# schematic.net
KiCad netlist of a schematic drawn in EAGLE
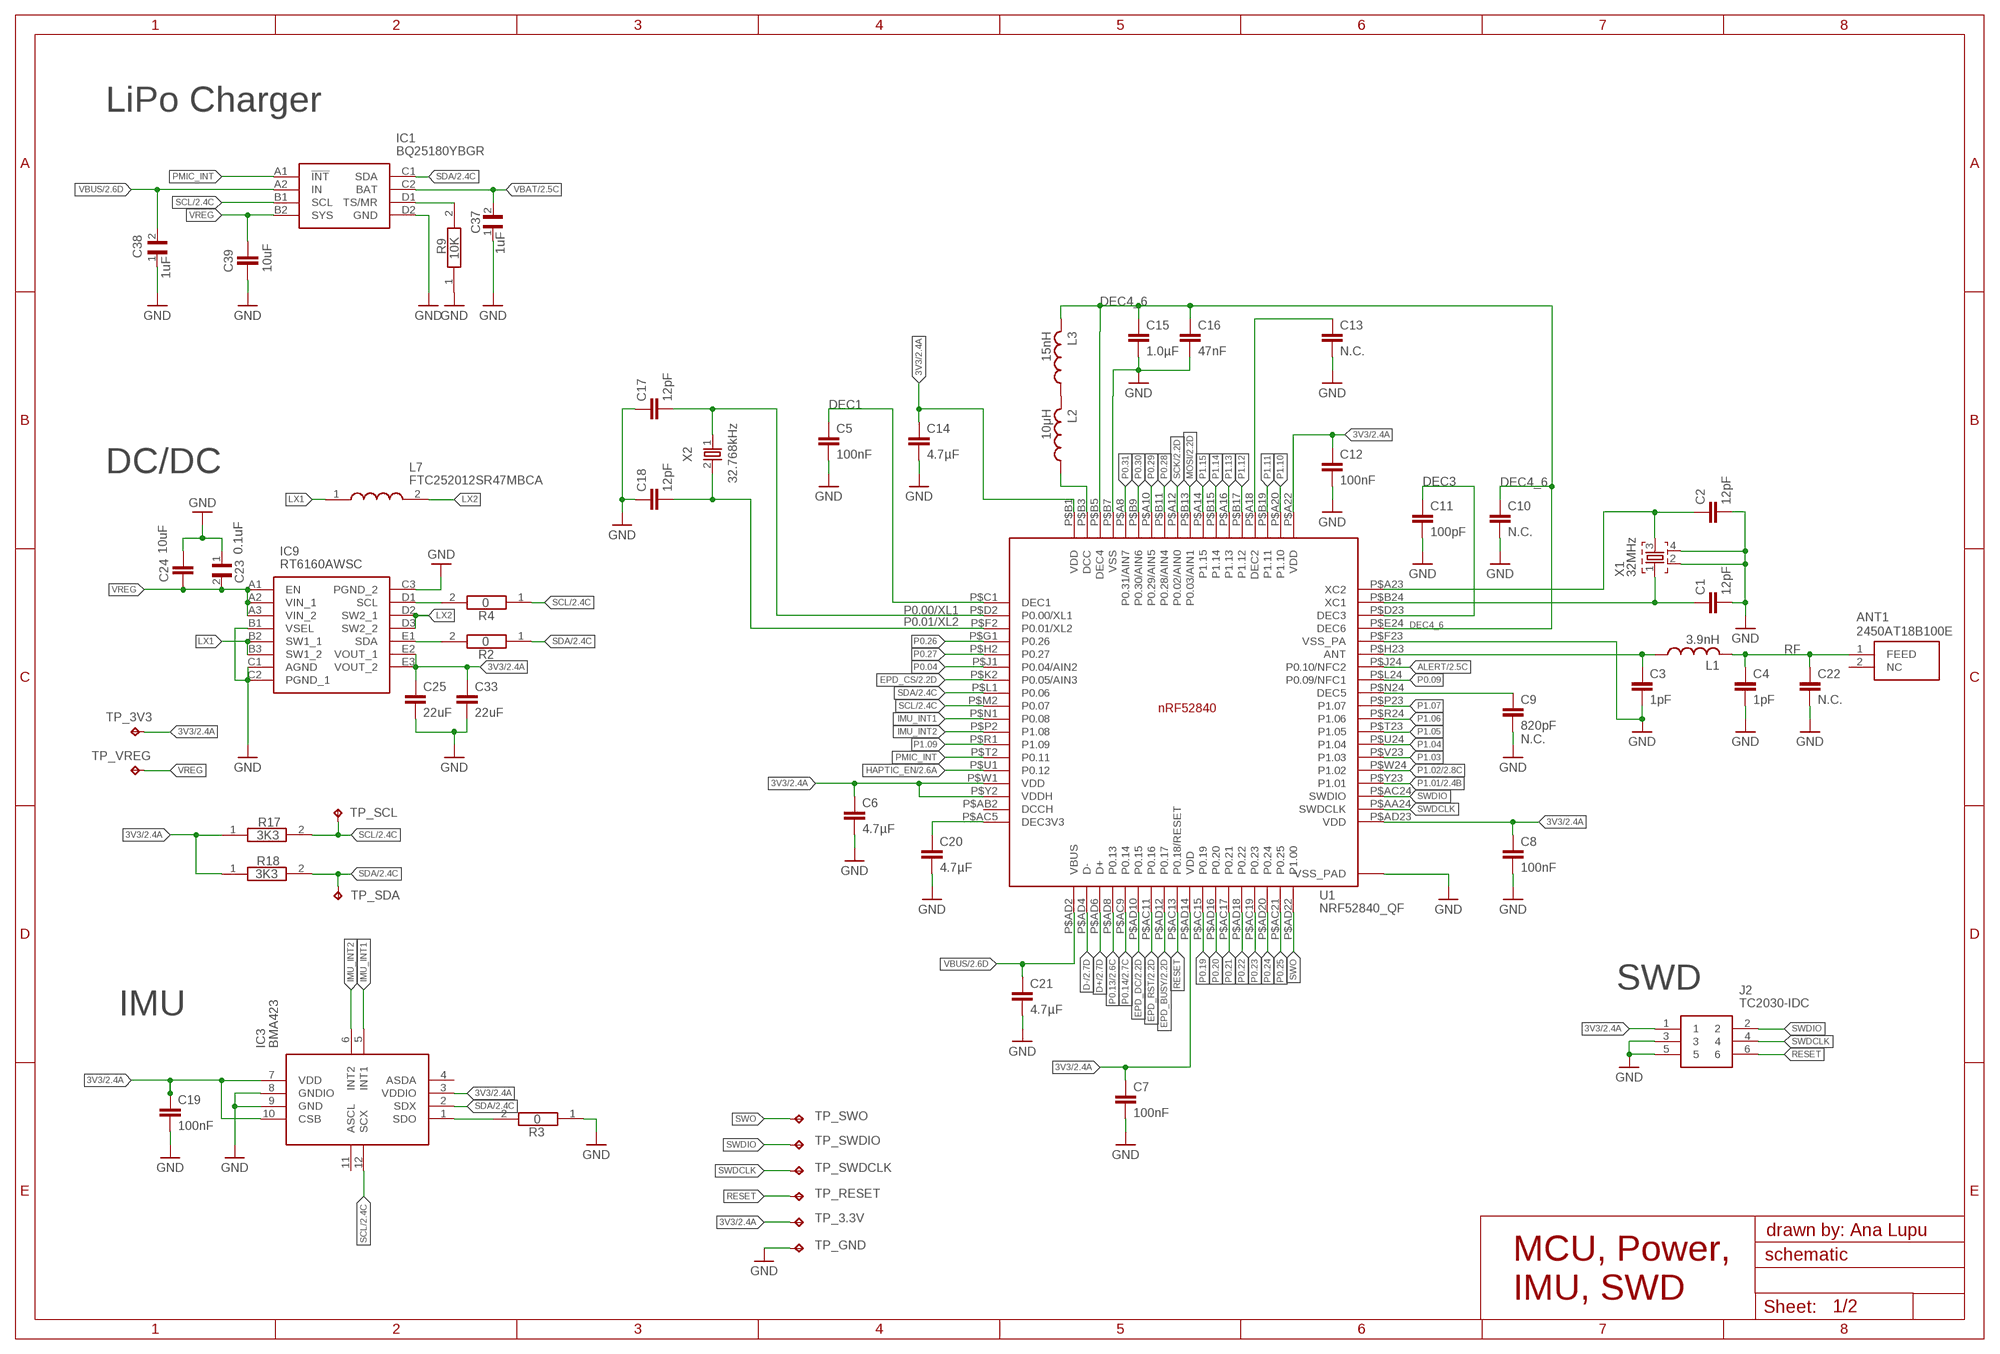
[diagram p0: schematic, sheet 1]
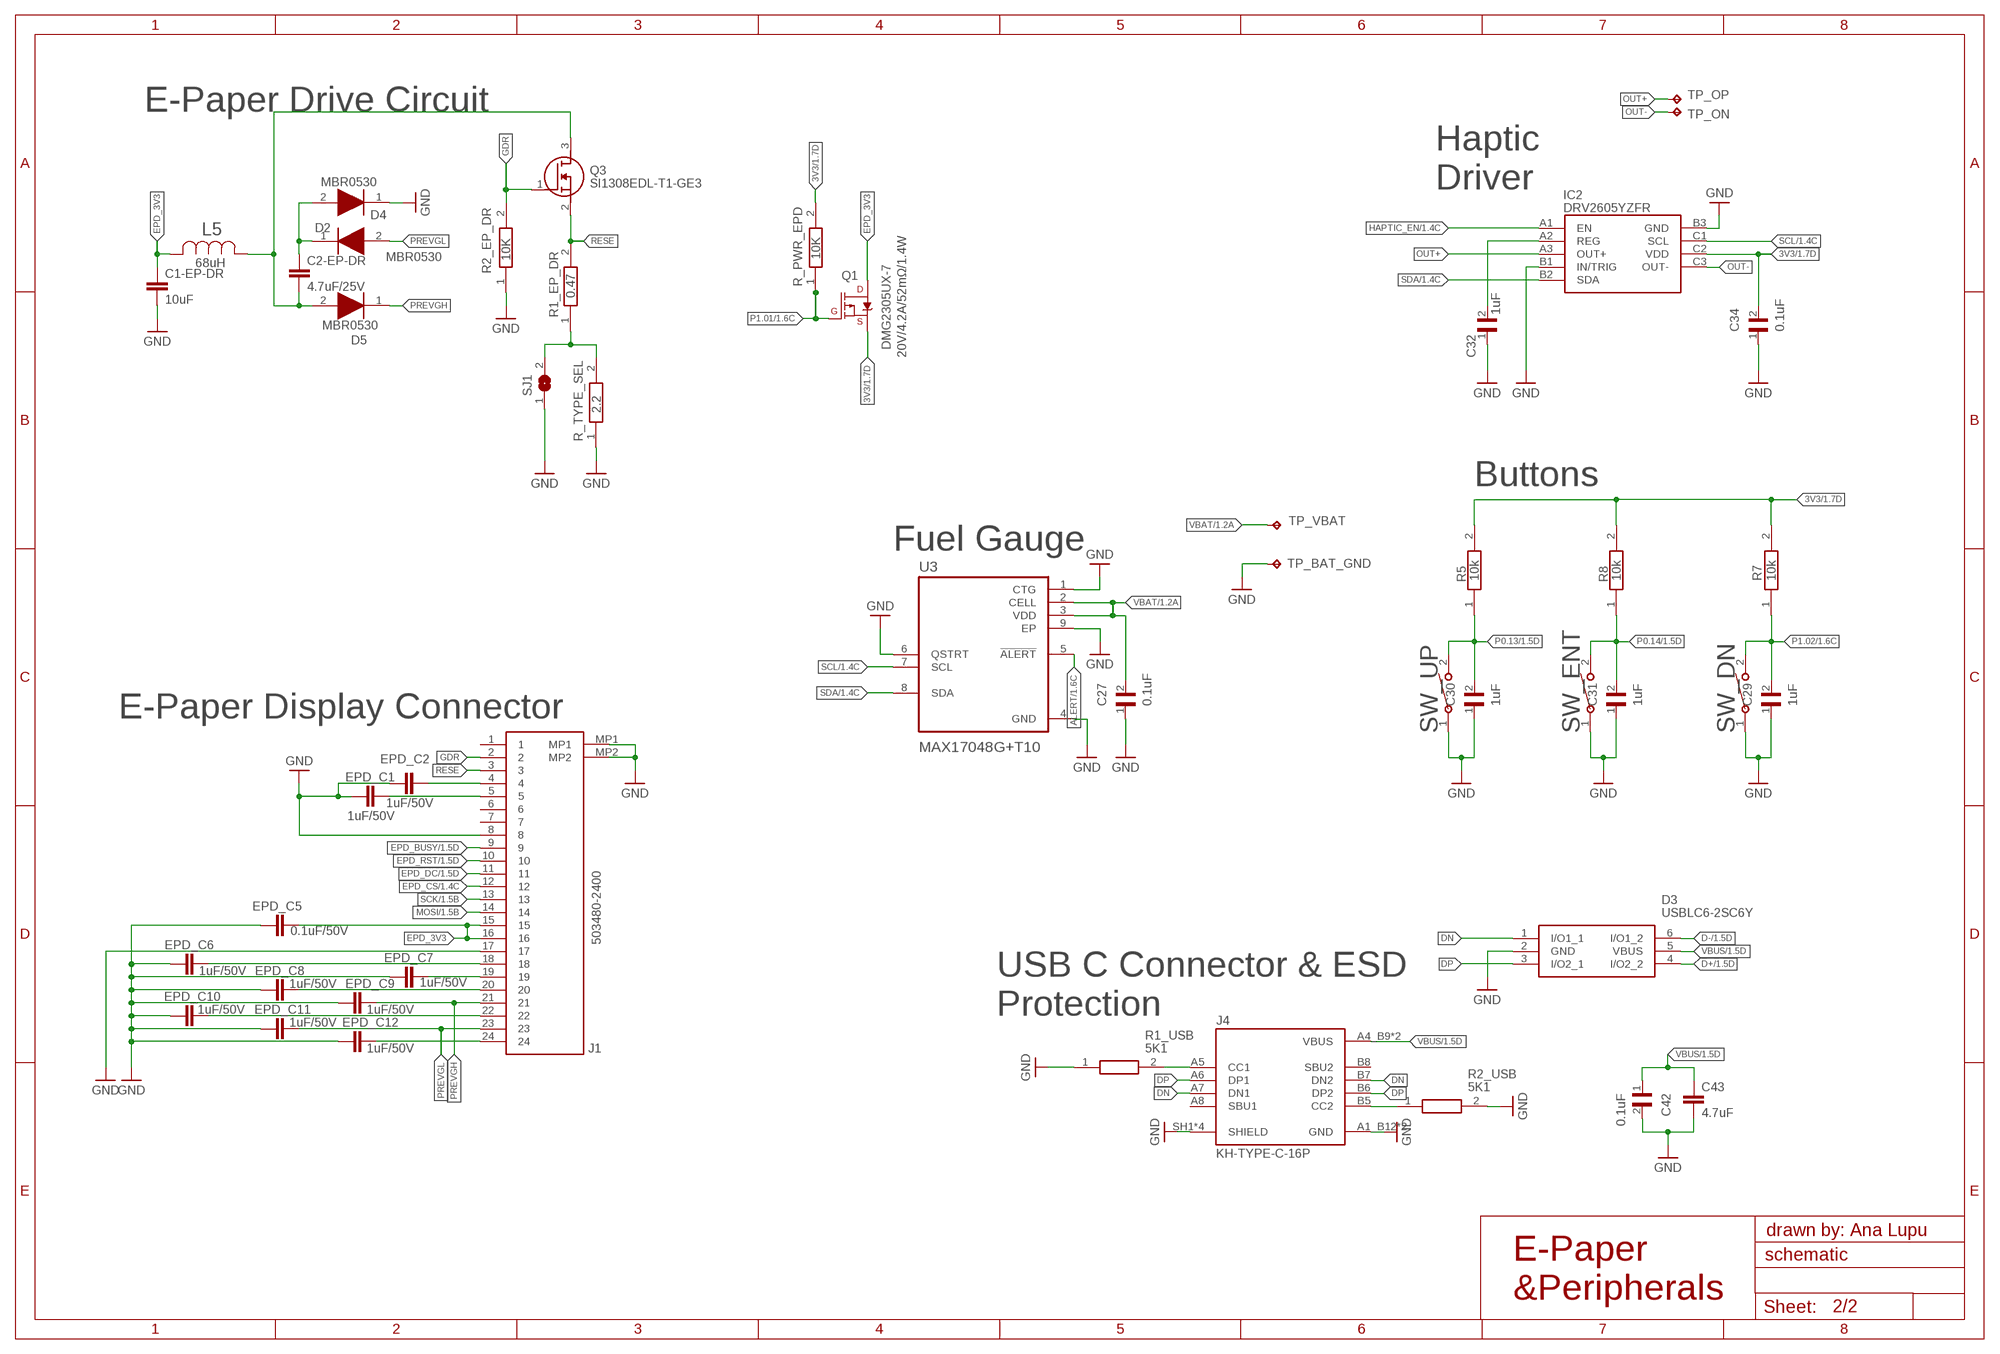
[diagram p1: schematic, sheet 2]

(export (version "E")
  (design (tool "Eeschema 10.0.6"))
  (components
    (comp (ref "C1-EP-DR")
      (value "10uF")
      (footprint "eagle-import:PERFECT_0402_0402")
      (libsource (lib "eagle-import") (part "InkTime_v5_vf.vX5wmjY0RqGaybr4i_JXZQ_PERFECT_0402_CAP_0402"))
    )
    (comp (ref "C2-EP-DR")
      (value "4.7uF/25V")
      (footprint "eagle-import:PERFECT_0402_0402")
      (libsource (lib "eagle-import") (part "InkTime_v5_vf.vX5wmjY0RqGaybr4i_JXZQ_PERFECT_0402_CAP_0402"))
    )
    (comp (ref "C27")
      (value "0.1uF")
      (footprint "eagle-import:GRM011R60J152KE01L_2_CAPC0201X13N")
      (fields (field (name "MF") "Murata") (field (name "MP") "GRM011R60J152KE01L"))
      (libsource (lib "eagle-import") (part "GRM011R60J152KE01L_2_GRM011R60J152KE01L"))
    )
    (comp (ref "C29")
      (value "1uF")
      (footprint "eagle-import:GRM011R60J152KE01L_2_CAPC0201X13N")
      (fields (field (name "MF") "Murata") (field (name "MP") "GRM011R60J152KE01L"))
      (libsource (lib "eagle-import") (part "GRM011R60J152KE01L_2_GRM011R60J152KE01L"))
    )
    (comp (ref "C30")
      (value "1uF")
      (footprint "eagle-import:GRM011R60J152KE01L_2_CAPC0201X13N")
      (fields (field (name "MF") "Murata") (field (name "MP") "GRM011R60J152KE01L"))
      (libsource (lib "eagle-import") (part "GRM011R60J152KE01L_2_GRM011R60J152KE01L"))
    )
    (comp (ref "C31")
      (value "1uF")
      (footprint "eagle-import:GRM011R60J152KE01L_2_CAPC0201X13N")
      (fields (field (name "MF") "Murata") (field (name "MP") "GRM011R60J152KE01L"))
      (libsource (lib "eagle-import") (part "GRM011R60J152KE01L_2_GRM011R60J152KE01L"))
    )
    (comp (ref "C32")
      (value "1uF")
      (footprint "eagle-import:GRM011R60J152KE01L_2_CAPC0201X13N")
      (fields (field (name "MF") "Murata") (field (name "MP") "GRM011R60J152KE01L"))
      (libsource (lib "eagle-import") (part "GRM011R60J152KE01L_2_GRM011R60J152KE01L"))
    )
    (comp (ref "C34")
      (value "0.1uF")
      (footprint "eagle-import:GRM011R60J152KE01L_2_CAPC0201X13N")
      (fields (field (name "MF") "Murata") (field (name "MP") "GRM011R60J152KE01L"))
      (libsource (lib "eagle-import") (part "GRM011R60J152KE01L_2_GRM011R60J152KE01L"))
    )
    (comp (ref "C42")
      (value "0.1uF")
      (footprint "eagle-import:GRM011R60J152KE01L_2_CAPC0201X13N")
      (fields (field (name "MF") "Murata") (field (name "MP") "GRM011R60J152KE01L"))
      (libsource (lib "eagle-import") (part "GRM011R60J152KE01L_2_GRM011R60J152KE01L"))
    )
    (comp (ref "C43")
      (value "4.7uF")
      (footprint "eagle-import:PERFECT_0402_0402")
      (libsource (lib "eagle-import") (part "InkTime_v5_vf.vX5wmjY0RqGaybr4i_JXZQ_PERFECT_0402_CAP_0402"))
    )
    (comp (ref "D2")
      (value "MBR0530")
      (footprint "eagle-import:ESP32_C6_LIBRARY_5_SOD3716X135N")
      (fields (field (name "MF") "ON Semiconductor"))
      (libsource (lib "eagle-import") (part "ESP32_C6_LIBRARY_5_MBR0530"))
    )
    (comp (ref "D3")
      (value "USBLC6-2SC6Y")
      (footprint "eagle-import:ESP32_C6_LIBRARY_3_SOT95P280X145-6N")
      (fields (field (name "MF") "STMicroelectronics"))
      (libsource (lib "eagle-import") (part "ESP32_C6_LIBRARY_3_USBLC6-2SC6Y"))
    )
    (comp (ref "D4")
      (value "MBR0530")
      (footprint "eagle-import:ESP32_C6_LIBRARY_5_SOD3716X135N")
      (fields (field (name "MF") "ON Semiconductor"))
      (libsource (lib "eagle-import") (part "ESP32_C6_LIBRARY_5_MBR0530"))
    )
    (comp (ref "D5")
      (value "MBR0530")
      (footprint "eagle-import:ESP32_C6_LIBRARY_5_SOD3716X135N")
      (fields (field (name "MF") "ON Semiconductor"))
      (libsource (lib "eagle-import") (part "ESP32_C6_LIBRARY_5_MBR0530"))
    )
    (comp (ref "DMG2305UX-7")
      (value "20V/4.2A/52mΩ/1.4W")
      (footprint "eagle-import:ESP32_C6_LIBRARY_4_ESP32_C6_LIBRARY_4_ESP32_C6_LIBRARY_4_ESP32_C6_LIBRARY_4_ESP32_WROVER_SPARKFUN-DISCRETESEMI_SOT23-3")
      (libsource (lib "eagle-import") (part "ESP32_C6_LIBRARY_4_ESP32_WROVER_SPARKFUN-DISCRETESEMI_MOSFET_PCH-DMG2305UX-7"))
    )
    (comp (ref "EPD_C1")
      (value "1uF/50V")
      (footprint "eagle-import:PERFECT_0402_0402")
      (libsource (lib "eagle-import") (part "InkTime_v5_vf.vX5wmjY0RqGaybr4i_JXZQ_PERFECT_0402_CAP_0402"))
    )
    (comp (ref "EPD_C2")
      (value "1uF/50V")
      (footprint "eagle-import:PERFECT_0402_0402")
      (libsource (lib "eagle-import") (part "PERFECT_0402_CAP_0402"))
    )
    (comp (ref "EPD_C5")
      (value "0.1uF/50V")
      (footprint "eagle-import:NORDIC_NRF_3_RESC0201_L")
      (libsource (lib "eagle-import") (part "NORDIC_NRF_3_CAPACITOR_0201_L"))
    )
    (comp (ref "EPD_C6")
      (value "1uF/50V")
      (footprint "eagle-import:PERFECT_0402_0402")
      (libsource (lib "eagle-import") (part "InkTime_v5_vf.vX5wmjY0RqGaybr4i_JXZQ_PERFECT_0402_CAP_0402"))
    )
    (comp (ref "EPD_C7")
      (value "1uF/50V")
      (footprint "eagle-import:PERFECT_0402_0402")
      (libsource (lib "eagle-import") (part "InkTime_v5_vf.vX5wmjY0RqGaybr4i_JXZQ_PERFECT_0402_CAP_0402"))
    )
    (comp (ref "EPD_C8")
      (value "1uF/50V")
      (footprint "eagle-import:PERFECT_0402_0402")
      (libsource (lib "eagle-import") (part "InkTime_v5_vf.vX5wmjY0RqGaybr4i_JXZQ_PERFECT_0402_CAP_0402"))
    )
    (comp (ref "EPD_C9")
      (value "1uF/50V")
      (footprint "eagle-import:PERFECT_0402_0402")
      (libsource (lib "eagle-import") (part "new_InkTime_v5_vf.bThMViGzTJemIPzQqDj0iw_PERFECT_0402_CAP_0402"))
    )
    (comp (ref "EPD_C10")
      (value "1uF/50V")
      (footprint "eagle-import:PERFECT_0402_0402")
      (libsource (lib "eagle-import") (part "InkTime_v5_vf.vX5wmjY0RqGaybr4i_JXZQ_PERFECT_0402_CAP_0402"))
    )
    (comp (ref "EPD_C11")
      (value "1uF/50V")
      (footprint "eagle-import:PERFECT_0402_0402")
      (libsource (lib "eagle-import") (part "InkTime_v5_vf.vX5wmjY0RqGaybr4i_JXZQ_PERFECT_0402_CAP_0402"))
    )
    (comp (ref "EPD_C12")
      (value "1uF/50V")
      (footprint "eagle-import:PERFECT_0402_0402")
      (libsource (lib "eagle-import") (part "InkTime_v5_vf.vX5wmjY0RqGaybr4i_JXZQ_PERFECT_0402_CAP_0402"))
    )
    (comp (ref "IC2")
      (value "DRV2605YZFR")
      (footprint "eagle-import:DRV2605YZFR_BGA9C50P3X3_144X144X62")
      (libsource (lib "eagle-import") (part "DRV2605YZFR_DRV2605YZFR"))
    )
    (comp (ref "J1")
      (value "503480-2400")
      (footprint "eagle-import:503480-2400_5034802400")
      (fields (field (name "MOUSER_PART_NUMBER") "538-503480-2400"))
      (libsource (lib "eagle-import") (part "503480-2400_503480-2400"))
    )
    (comp (ref "J4")
      (value "KH-TYPE-C-16P")
      (footprint "eagle-import:KH-TYPE-C-16P_KINGHELM_KH-TYPE-C-16P")
      (fields (field (name "MF") "kinghelm"))
      (libsource (lib "eagle-import") (part "KH-TYPE-C-16P_KH-TYPE-C-16P"))
    )
    (comp (ref "L5")
      (value "68uH")
      (footprint "eagle-import:ESP32_C6_LIBRARY_2_IND_4828-WE-TPC_WRE")
      (fields
        (field (name "MANUFACTURER_PART_NUMBER") "744043680")
        (field (name "COPYRIGHT") "Copyright (C) 2024 Ultra Librarian. All rights reserved.")
      )
      (libsource (lib "eagle-import") (part "ESP32_C6_LIBRARY_2_744043680IND_4828-WE-TPC_WRE"))
    )
    (comp (ref "Q3")
      (value "SI1308EDL-T1-GE3")
      (footprint "eagle-import:ESP32_C6_LIBRARY_6_SOT65P210X110-3N")
      (fields (field (name "MF") "Vishay Siliconix"))
      (libsource (lib "eagle-import") (part "ESP32_C6_LIBRARY_6_SI1308EDL-T1-GE3"))
    )
    (comp (ref "R1_EP_DR")
      (value "0.47")
      (footprint "eagle-import:ERA-1AEB3401C_0201")
      (libsource (lib "eagle-import") (part "ERA-1AEB3401C_CPF0201D7K68C1"))
    )
    (comp (ref "R1_USB")
      (value "5K1")
      (footprint "eagle-import:ERA-1AEB3401C_0201")
      (libsource (lib "eagle-import") (part "ERA-1AEB3401C_CPF0201D7K68C1"))
    )
    (comp (ref "R2_EP_DR")
      (value "10K")
      (footprint "eagle-import:ERA-1AEB3401C_0201")
      (libsource (lib "eagle-import") (part "ERA-1AEB3401C_CPF0201D7K68C1"))
    )
    (comp (ref "R2_USB")
      (value "5K1")
      (footprint "eagle-import:ERA-1AEB3401C_0201")
      (libsource (lib "eagle-import") (part "ERA-1AEB3401C_CPF0201D7K68C1"))
    )
    (comp (ref "R5")
      (value "10k")
      (footprint "eagle-import:ERA-1AEB3401C_0201")
      (libsource (lib "eagle-import") (part "ERA-1AEB3401C_CPF0201D7K68C1"))
    )
    (comp (ref "R7")
      (value "10k")
      (footprint "eagle-import:ERA-1AEB3401C_0201")
      (libsource (lib "eagle-import") (part "ERA-1AEB3401C_CPF0201D7K68C1"))
    )
    (comp (ref "R8")
      (value "10k")
      (footprint "eagle-import:ERA-1AEB3401C_0201")
      (libsource (lib "eagle-import") (part "ERA-1AEB3401C_CPF0201D7K68C1"))
    )
    (comp (ref "R_PWR_EPD")
      (value "10K")
      (footprint "eagle-import:ERA-1AEB3401C_0201")
      (libsource (lib "eagle-import") (part "ERA-1AEB3401C_CPF0201D7K68C1"))
    )
    (comp (ref "R_TYPE_SEL")
      (value "2.2")
      (footprint "eagle-import:ERA-1AEB3401C_0201")
      (libsource (lib "eagle-import") (part "ERA-1AEB3401C_CPF0201D7K68C1"))
    )
    (comp (ref "SJ1")
      (value "ESP32_C6_LIBRARY_7_JUMPER_SJ")
      (footprint "eagle-import:ESP32_C6_LIBRARY_7_JUMPER_SJ")
      (libsource (lib "eagle-import") (part "ESP32_C6_LIBRARY_7_JUMPER_SJ"))
    )
    (comp (ref "SW_DN")
      (value "2025-10-22_07-23-44_LIBRARY_EVP-AKE31ASW_EVP-AKE31A_PAN")
      (footprint "eagle-import:2025-10-22_07-23-44_LIBRARY_SW_EVP-AKE31A_PAN")
      (fields
        (field (name "MANUFACTURER_PART_NUMBER") "EVP-AKE31A")
        (field (name "COPYRIGHT") "Copyright (C) 2025 Ultra Librarian. All rights reserved.")
      )
      (libsource (lib "eagle-import") (part "2025-10-22_07-23-44_LIBRARY_EVP-AKE31ASW_EVP-AKE31A_PAN"))
    )
    (comp (ref "SW_ENT")
      (value "2025-10-22_07-23-44_LIBRARY_EVP-AKE31ASW_EVP-AKE31A_PAN")
      (footprint "eagle-import:2025-10-22_07-23-44_LIBRARY_SW_EVP-AKE31A_PAN")
      (fields
        (field (name "MANUFACTURER_PART_NUMBER") "EVP-AKE31A")
        (field (name "COPYRIGHT") "Copyright (C) 2025 Ultra Librarian. All rights reserved.")
      )
      (libsource (lib "eagle-import") (part "2025-10-22_07-23-44_LIBRARY_EVP-AKE31ASW_EVP-AKE31A_PAN"))
    )
    (comp (ref "SW_UP")
      (value "2025-10-22_07-23-44_LIBRARY_EVP-AKE31ASW_EVP-AKE31A_PAN")
      (footprint "eagle-import:2025-10-22_07-23-44_LIBRARY_SW_EVP-AKE31A_PAN")
      (fields
        (field (name "MANUFACTURER_PART_NUMBER") "EVP-AKE31A")
        (field (name "COPYRIGHT") "Copyright (C) 2025 Ultra Librarian. All rights reserved.")
      )
      (libsource (lib "eagle-import") (part "2025-10-22_07-23-44_LIBRARY_EVP-AKE31ASW_EVP-AKE31A_PAN"))
    )
    (comp (ref "TP_BAT_GND")
      (value "HECTOR_WATCH_1_TPTP20R")
      (footprint "eagle-import:HECTOR_WATCH_1_TP20R")
      (libsource (lib "eagle-import") (part "HECTOR_WATCH_1_TPTP20R"))
    )
    (comp (ref "TP_ON")
      (value "HECTOR_WATCH_1_TPTP20R")
      (footprint "eagle-import:HECTOR_WATCH_1_TP20R")
      (libsource (lib "eagle-import") (part "HECTOR_WATCH_1_TPTP20R"))
    )
    (comp (ref "TP_OP")
      (value "HECTOR_WATCH_1_TPTP20R")
      (footprint "eagle-import:HECTOR_WATCH_1_TP20R")
      (libsource (lib "eagle-import") (part "HECTOR_WATCH_1_TPTP20R"))
    )
    (comp (ref "TP_VBAT")
      (value "HECTOR_WATCH_1_TPTP20R")
      (footprint "eagle-import:HECTOR_WATCH_1_TP20R")
      (libsource (lib "eagle-import") (part "HECTOR_WATCH_1_TPTP20R"))
    )
    (comp (ref "U3")
      (value "MAX17048G+T10")
      (footprint "eagle-import:ESP32_C6_LIBRARY_SON50P200X200X80-9N")
      (fields (field (name "MF") "Analog Devices"))
      (libsource (lib "eagle-import") (part "ESP32_C6_LIBRARY_MAX17048G+T10"))
    )
    (comp (ref "ANT1")
      (value "2450AT18B100E")
      (footprint "eagle-import:2450AT18B100E_ANTC3216X140N")
      (fields (field (name "MOUSER_PART_NUMBER") "609-2450AT18B100E"))
      (libsource (lib "eagle-import") (part "2450AT18B100E_2450AT18B100E"))
    )
    (comp (ref "C1")
      (value "12pF")
      (footprint "eagle-import:NORDIC_NRF_3_RESC0201_L")
      (libsource (lib "eagle-import") (part "NORDIC_NRF_3_CAPACITOR_0201_L"))
    )
    (comp (ref "C2")
      (value "12pF")
      (footprint "eagle-import:NORDIC_NRF_3_RESC0201_L")
      (libsource (lib "eagle-import") (part "NORDIC_NRF_3_CAPACITOR_0201_L"))
    )
    (comp (ref "C3")
      (value "1pF")
      (footprint "eagle-import:NORDIC_NRF_3_RESC0201_L")
      (libsource (lib "eagle-import") (part "NORDIC_NRF_3_CAPACITOR_0201_L"))
    )
    (comp (ref "C4")
      (value "1pF")
      (footprint "eagle-import:NORDIC_NRF_3_RESC0201_L")
      (libsource (lib "eagle-import") (part "NORDIC_NRF_3_CAPACITOR_0201_L"))
    )
    (comp (ref "C5")
      (value "100nF")
      (footprint "eagle-import:NORDIC_NRF_3_RESC0201_L")
      (libsource (lib "eagle-import") (part "NORDIC_NRF_3_CAPACITOR_0201_L"))
    )
    (comp (ref "C6")
      (value "4.7µF")
      (footprint "eagle-import:PERFECT_0402_0402")
      (libsource (lib "eagle-import") (part "InkTime_v5_vf.vX5wmjY0RqGaybr4i_JXZQ_PERFECT_0402_CAP_0402"))
    )
    (comp (ref "C7")
      (value "100nF")
      (footprint "eagle-import:NORDIC_NRF_3_RESC0201_L")
      (libsource (lib "eagle-import") (part "NORDIC_NRF_3_CAPACITOR_0201_L"))
    )
    (comp (ref "C8")
      (value "100nF")
      (footprint "eagle-import:NORDIC_NRF_3_RESC0201_L")
      (libsource (lib "eagle-import") (part "NORDIC_NRF_3_CAPACITOR_0201_L"))
    )
    (comp (ref "C9")
      (value "820pF")
      (footprint "eagle-import:NORDIC_NRF_3_RESC0201_L")
      (libsource (lib "eagle-import") (part "NORDIC_NRF_3_CAPACITOR_0201_L"))
    )
    (comp (ref "C10")
      (value "N.C.")
      (footprint "eagle-import:NORDIC_NRF_3_RESC0201_L")
      (libsource (lib "eagle-import") (part "NORDIC_NRF_3_CAPACITOR_0201_L"))
    )
    (comp (ref "C11")
      (value "100pF")
      (footprint "eagle-import:NORDIC_NRF_3_RESC0201_L")
      (libsource (lib "eagle-import") (part "NORDIC_NRF_3_CAPACITOR_0201_L"))
    )
    (comp (ref "C12")
      (value "100nF")
      (footprint "eagle-import:NORDIC_NRF_3_RESC0201_L")
      (libsource (lib "eagle-import") (part "NORDIC_NRF_3_CAPACITOR_0201_L"))
    )
    (comp (ref "C13")
      (value "N.C.")
      (footprint "eagle-import:NORDIC_NRF_3_RESC0201_L")
      (libsource (lib "eagle-import") (part "NORDIC_NRF_3_CAPACITOR_0201_L"))
    )
    (comp (ref "C14")
      (value "4.7µF")
      (footprint "eagle-import:PERFECT_0402_0402")
      (libsource (lib "eagle-import") (part "InkTime_v5_vf.vX5wmjY0RqGaybr4i_JXZQ_PERFECT_0402_CAP_0402"))
    )
    (comp (ref "C15")
      (value "1.0µF")
      (footprint "eagle-import:PERFECT_0402_0402")
      (libsource (lib "eagle-import") (part "InkTime_v5_vf.vX5wmjY0RqGaybr4i_JXZQ_PERFECT_0402_CAP_0402"))
    )
    (comp (ref "C16")
      (value "47nF")
      (footprint "eagle-import:NORDIC_NRF_3_RESC0201_L")
      (libsource (lib "eagle-import") (part "NORDIC_NRF_3_CAPACITOR_0201_L"))
    )
    (comp (ref "C17")
      (value "12pF")
      (footprint "eagle-import:NORDIC_NRF_3_RESC0201_L")
      (libsource (lib "eagle-import") (part "NORDIC_NRF_3_CAPACITOR_0201_L"))
    )
    (comp (ref "C18")
      (value "12pF")
      (footprint "eagle-import:NORDIC_NRF_3_RESC0201_L")
      (libsource (lib "eagle-import") (part "NORDIC_NRF_3_CAPACITOR_0201_L"))
    )
    (comp (ref "C19")
      (value "100nF")
      (footprint "eagle-import:NORDIC_NRF_3_RESC0201_L")
      (libsource (lib "eagle-import") (part "NORDIC_NRF_3_CAPACITOR_0201_L"))
    )
    (comp (ref "C20")
      (value "4.7µF")
      (footprint "eagle-import:PERFECT_0402_0402")
      (libsource (lib "eagle-import") (part "InkTime_v5_vf.vX5wmjY0RqGaybr4i_JXZQ_PERFECT_0402_CAP_0402"))
    )
    (comp (ref "C21")
      (value "4.7µF")
      (footprint "eagle-import:PERFECT_0402_0402")
      (libsource (lib "eagle-import") (part "InkTime_v5_vf.vX5wmjY0RqGaybr4i_JXZQ_PERFECT_0402_CAP_0402"))
    )
    (comp (ref "C22")
      (value "N.C.")
      (footprint "eagle-import:NORDIC_NRF_3_RESC0201_L")
      (libsource (lib "eagle-import") (part "NORDIC_NRF_3_CAPACITOR_0201_L"))
    )
    (comp (ref "C23")
      (value "0.1uF")
      (footprint "eagle-import:GRM011R60J152KE01L_2_CAPC0201X13N")
      (fields (field (name "MF") "Murata") (field (name "MP") "GRM011R60J152KE01L"))
      (libsource (lib "eagle-import") (part "GRM011R60J152KE01L_2_GRM011R60J152KE01L"))
    )
    (comp (ref "C24")
      (value "10uF")
      (footprint "eagle-import:PERFECT_0402_0402")
      (libsource (lib "eagle-import") (part "InkTime_v5_vf.vX5wmjY0RqGaybr4i_JXZQ_PERFECT_0402_CAP_0402"))
    )
    (comp (ref "C25")
      (value "22uF")
      (footprint "eagle-import:PERFECT_0402_0402")
      (libsource (lib "eagle-import") (part "InkTime_v5_vf.vX5wmjY0RqGaybr4i_JXZQ_PERFECT_0402_CAP_0402"))
    )
    (comp (ref "C33")
      (value "22uF")
      (footprint "eagle-import:PERFECT_0402_0402")
      (libsource (lib "eagle-import") (part "InkTime_v5_vf.vX5wmjY0RqGaybr4i_JXZQ_PERFECT_0402_CAP_0402"))
    )
    (comp (ref "C37")
      (value "1uF")
      (footprint "eagle-import:GRM011R60J152KE01L_2_CAPC0201X13N")
      (fields (field (name "MF") "Murata") (field (name "MP") "GRM011R60J152KE01L"))
      (libsource (lib "eagle-import") (part "GRM011R60J152KE01L_2_GRM011R60J152KE01L"))
    )
    (comp (ref "C38")
      (value "1uF")
      (footprint "eagle-import:GRM011R60J152KE01L_2_CAPC0201X13N")
      (fields (field (name "MF") "Murata") (field (name "MP") "GRM011R60J152KE01L"))
      (libsource (lib "eagle-import") (part "GRM011R60J152KE01L_2_GRM011R60J152KE01L"))
    )
    (comp (ref "C39")
      (value "10uF")
      (footprint "eagle-import:PERFECT_0402_0402")
      (libsource (lib "eagle-import") (part "InkTime_v5_vf.vX5wmjY0RqGaybr4i_JXZQ_PERFECT_0402_CAP_0402"))
    )
    (comp (ref "IC1")
      (value "BQ25180YBGR")
      (footprint "eagle-import:BQ25180YBGR_BGA8C40P2X4_100X155X50")
      (fields (field (name "MOUSER_PART_NUMBER") "595-BQ25180YBGR"))
      (libsource (lib "eagle-import") (part "BQ25180YBGR_BQ25180YBGR"))
    )
    (comp (ref "IC3")
      (value "BMA423")
      (footprint "eagle-import:BMA423_BMA423")
      (fields (field (name "MOUSER_PART_NUMBER") "262-BMA423"))
      (libsource (lib "eagle-import") (part "BMA423_BMA423"))
    )
    (comp (ref "IC9")
      (value "RT6160AWSC")
      (footprint "eagle-import:RT6160AWSC_BGA15C40P3X5_140X230X60")
      (fields (field (name "MOUSER_PART_NUMBER") "835-RT6160AWSC"))
      (libsource (lib "eagle-import") (part "RT6160AWSC_RT6160AWSC"))
    )
    (comp (ref "J2")
      (value "TC2030-IDC")
      (footprint "eagle-import:TC2030-IDC_TC2030IDC")
      (libsource (lib "eagle-import") (part "TC2030-IDC_TC2030-IDC"))
    )
    (comp (ref "L1")
      (value "3.9nH")
      (footprint "eagle-import:NORDIC_NRF_2_RESC0402_M")
      (libsource (lib "eagle-import") (part "NORDIC_NRF_2_INDUCTOR_0402_M"))
    )
    (comp (ref "L2")
      (value "10μH")
      (footprint "eagle-import:NORDIC_NRF_2_RESC0402_M")
      (libsource (lib "eagle-import") (part "NORDIC_NRF_2_INDUCTOR_0402_M"))
    )
    (comp (ref "L3")
      (value "15nH")
      (footprint "eagle-import:NORDIC_NRF_2_RESC0402_M")
      (libsource (lib "eagle-import") (part "NORDIC_NRF_2_INDUCTOR_0402_M"))
    )
    (comp (ref "L7")
      (value "FTC252012SR47MBCA")
      (footprint "eagle-import:MLP2016SR47MT0S1_INDC2016X100N")
      (libsource (lib "eagle-import") (part "MLP2016SR47MT0S1_FTC252012SR47MBCA"))
    )
    (comp (ref "R2")
      (value "0")
      (footprint "eagle-import:CPF0201D7K68C1_0201")
      (libsource (lib "eagle-import") (part "CPF0201D7K68C1_CPF0201D7K68C1"))
    )
    (comp (ref "R3")
      (value "0")
      (footprint "eagle-import:CPF0201D7K68C1_0201")
      (libsource (lib "eagle-import") (part "CPF0201D7K68C1_CPF0201D7K68C1"))
    )
    (comp (ref "R4")
      (value "0")
      (footprint "eagle-import:CPF0201D7K68C1_0201")
      (libsource (lib "eagle-import") (part "CPF0201D7K68C1_CPF0201D7K68C1"))
    )
    (comp (ref "R9")
      (value "10K")
      (footprint "eagle-import:CPF0201D7K68C1_0201")
      (libsource (lib "eagle-import") (part "CPF0201D7K68C1_CPF0201D7K68C1"))
    )
    (comp (ref "R17")
      (value "3K3")
      (footprint "eagle-import:CPF0201D7K68C1_0201")
      (libsource (lib "eagle-import") (part "CPF0201D7K68C1_CPF0201D7K68C1"))
    )
    (comp (ref "R18")
      (value "3K3")
      (footprint "eagle-import:CPF0201D7K68C1_0201")
      (libsource (lib "eagle-import") (part "CPF0201D7K68C1_CPF0201D7K68C1"))
    )
    (comp (ref "TP_3.3V")
      (value "HECTOR_WATCH_1_TPTP20R")
      (footprint "eagle-import:HECTOR_WATCH_1_TP20R")
      (libsource (lib "eagle-import") (part "HECTOR_WATCH_1_TPTP20R"))
    )
    (comp (ref "TP_3V3")
      (value "HECTOR_WATCH_1_TPTP20R")
      (footprint "eagle-import:HECTOR_WATCH_1_TP20R")
      (libsource (lib "eagle-import") (part "HECTOR_WATCH_1_TPTP20R"))
    )
    (comp (ref "TP_GND")
      (value "HECTOR_WATCH_1_TPTP20R")
      (footprint "eagle-import:HECTOR_WATCH_1_TP20R")
      (libsource (lib "eagle-import") (part "HECTOR_WATCH_1_TPTP20R"))
    )
    (comp (ref "TP_RESET")
      (value "HECTOR_WATCH_1_TPTP20R")
      (footprint "eagle-import:HECTOR_WATCH_1_TP20R")
      (libsource (lib "eagle-import") (part "HECTOR_WATCH_1_TPTP20R"))
    )
    (comp (ref "TP_SCL")
      (value "HECTOR_WATCH_1_TPTP20R")
      (footprint "eagle-import:HECTOR_WATCH_1_TP20R")
      (libsource (lib "eagle-import") (part "HECTOR_WATCH_1_TPTP20R"))
    )
    (comp (ref "TP_SDA")
      (value "HECTOR_WATCH_1_TPTP20R")
      (footprint "eagle-import:HECTOR_WATCH_1_TP20R")
      (libsource (lib "eagle-import") (part "HECTOR_WATCH_1_TPTP20R"))
    )
    (comp (ref "TP_SWDCLK")
      (value "HECTOR_WATCH_1_TPTP20R")
      (footprint "eagle-import:HECTOR_WATCH_1_TP20R")
      (libsource (lib "eagle-import") (part "HECTOR_WATCH_1_TPTP20R"))
    )
    (comp (ref "TP_SWDIO")
      (value "HECTOR_WATCH_1_TPTP20R")
      (footprint "eagle-import:HECTOR_WATCH_1_TP20R")
      (libsource (lib "eagle-import") (part "HECTOR_WATCH_1_TPTP20R"))
    )
    (comp (ref "TP_SWO")
      (value "HECTOR_WATCH_1_TPTP20R")
      (footprint "eagle-import:HECTOR_WATCH_1_TP20R")
      (libsource (lib "eagle-import") (part "HECTOR_WATCH_1_TPTP20R"))
    )
    (comp (ref "TP_VREG")
      (value "HECTOR_WATCH_1_TPTP20R")
      (footprint "eagle-import:HECTOR_WATCH_1_TP20R")
      (libsource (lib "eagle-import") (part "HECTOR_WATCH_1_TPTP20R"))
    )
    (comp (ref "U1")
      (value "NRF52840_QF")
      (footprint "eagle-import:NORDIC_NRF_4_AQFN50P700X700X85_HS-74N")
      (libsource (lib "eagle-import") (part "NORDIC_NRF_4_NRF52840_QF"))
    )
    (comp (ref "X1")
      (value "32MHz")
      (footprint "eagle-import:NORDIC_NRF_BT-XTAL_2016_N")
      (libsource (lib "eagle-import") (part "NORDIC_NRF_XTAL_32MHZ"))
    )
    (comp (ref "X2")
      (value "32.768kHz")
      (footprint "eagle-import:NORDIC_NRF_1_XTAL_3215_N")
      (libsource (lib "eagle-import") (part "NORDIC_NRF_1_XTAL_32KHZ"))
    )
  )
  (nets
    (net (code "1") (name "3V3{slash}1.7D") (class "Default")
      (node (ref "C34") (pin "2") (pinfunction "2_2") (pintype "passive"))
      (node (ref "DMG2305UX-7") (pin "2") (pinfunction "S_2") (pintype "bidirectional"))
      (node (ref "IC2") (pin "C2") (pinfunction "VDD_C2") (pintype "bidirectional"))
      (node (ref "R5") (pin "2") (pinfunction "2_2") (pintype "bidirectional"))
      (node (ref "R7") (pin "2") (pinfunction "2_2") (pintype "bidirectional"))
      (node (ref "R8") (pin "2") (pinfunction "2_2") (pintype "bidirectional"))
      (node (ref "R_PWR_EPD") (pin "2") (pinfunction "2_2") (pintype "bidirectional"))
    )
    (net (code "2") (name "3V3{slash}2.4A") (class "Default")
      (node (ref "C12") (pin "1") (pinfunction "1_1") (pintype "passive"))
      (node (ref "C14") (pin "1") (pinfunction "1_1") (pintype "passive"))
      (node (ref "C19") (pin "1") (pinfunction "1_1") (pintype "passive"))
      (node (ref "C25") (pin "1") (pinfunction "1_1") (pintype "passive"))
      (node (ref "C33") (pin "1") (pinfunction "1_1") (pintype "passive"))
      (node (ref "C6") (pin "1") (pinfunction "1_1") (pintype "passive"))
      (node (ref "C7") (pin "1") (pinfunction "1_1") (pintype "passive"))
      (node (ref "C8") (pin "1") (pinfunction "1_1") (pintype "passive"))
      (node (ref "IC3") (pin "10") (pinfunction "CSB_10") (pintype "bidirectional"))
      (node (ref "IC3") (pin "3") (pinfunction "VDDIO_3") (pintype "bidirectional"))
      (node (ref "IC3") (pin "7") (pinfunction "VDD_7") (pintype "bidirectional"))
      (node (ref "IC9") (pin "E2") (pinfunction "VOUT_1_E2") (pintype "bidirectional"))
      (node (ref "IC9") (pin "E3") (pinfunction "VOUT_2_E3") (pintype "bidirectional"))
      (node (ref "J2") (pin "1") (pinfunction "1_1") (pintype "bidirectional"))
      (node (ref "R17") (pin "1") (pinfunction "1_1") (pintype "bidirectional"))
      (node (ref "R18") (pin "1") (pinfunction "1_1") (pintype "bidirectional"))
      (node (ref "TP_3.3V") (pin "TP") (pinfunction "TP_TP") (pintype "input"))
      (node (ref "TP_3V3") (pin "TP") (pinfunction "TP_TP") (pintype "input"))
      (node (ref "U1") (pin "P$A22") (pinfunction "VDD_P$A22") (pintype "power_in"))
      (node (ref "U1") (pin "P$AD14") (pinfunction "VDD_P$AD14") (pintype "power_in"))
      (node (ref "U1") (pin "P$AD23") (pinfunction "VDD_P$AD23") (pintype "power_in"))
      (node (ref "U1") (pin "P$B1") (pinfunction "VDD_P$B1") (pintype "power_in"))
      (node (ref "U1") (pin "P$W1") (pinfunction "VDD_P$W1") (pintype "power_in"))
      (node (ref "U1") (pin "P$Y2") (pinfunction "VDDH_P$Y2") (pintype "power_in"))
    )
    (net (code "3") (name "ALERT{slash}1.6C") (class "Default")
      (node (ref "U3") (pin "5") (pinfunction "~{ALERT}_5") (pintype "output"))
    )
    (net (code "4") (name "ALERT{slash}2.5C") (class "Default")
      (node (ref "U1") (pin "P$J24") (pinfunction "P0.10/NFC2_P$J24") (pintype "bidirectional"))
    )
    (net (code "5") (name "D+{slash}1.5D") (class "Default")
      (node (ref "D3") (pin "4") (pinfunction "I/O2_2_4") (pintype "bidirectional"))
    )
    (net (code "6") (name "D+{slash}2.7D") (class "Default")
      (node (ref "U1") (pin "P$AD6") (pinfunction "D+_P$AD6") (pintype "bidirectional"))
    )
    (net (code "7") (name "D-{slash}1.5D") (class "Default")
      (node (ref "D3") (pin "6") (pinfunction "I/O1_2_6") (pintype "bidirectional"))
    )
    (net (code "8") (name "D-{slash}2.7D") (class "Default")
      (node (ref "U1") (pin "P$AD4") (pinfunction "D-_P$AD4") (pintype "bidirectional"))
    )
    (net (code "9") (name "DEC4_6") (class "Default")
      (node (ref "C10") (pin "1") (pinfunction "1_1") (pintype "passive"))
      (node (ref "C15") (pin "1") (pinfunction "1_1") (pintype "passive"))
      (node (ref "C16") (pin "1") (pinfunction "1_1") (pintype "passive"))
      (node (ref "L3") (pin "2") (pinfunction "2_2") (pintype "passive"))
      (node (ref "U1") (pin "P$B5") (pinfunction "DEC4_P$B5") (pintype "power_in"))
      (node (ref "U1") (pin "P$E24") (pinfunction "DEC6_P$E24") (pintype "bidirectional"))
    )
    (net (code "10") (name "DN") (class "Default")
      (node (ref "D3") (pin "1") (pinfunction "I/O1_1_1") (pintype "bidirectional"))
      (node (ref "J4") (pin "A7") (pinfunction "DN1_A7") (pintype "bidirectional"))
      (node (ref "J4") (pin "B7") (pinfunction "DN2_B7") (pintype "bidirectional"))
    )
    (net (code "11") (name "DP") (class "Default")
      (node (ref "D3") (pin "3") (pinfunction "I/O2_1_3") (pintype "bidirectional"))
      (node (ref "J4") (pin "A6") (pinfunction "DP1_A6") (pintype "bidirectional"))
      (node (ref "J4") (pin "B6") (pinfunction "DP2_B6") (pintype "bidirectional"))
    )
    (net (code "12") (name "EPD_3V3") (class "Default")
      (node (ref "C1-EP-DR") (pin "1") (pinfunction "1_1") (pintype "passive"))
      (node (ref "DMG2305UX-7") (pin "3") (pinfunction "D_3") (pintype "bidirectional"))
      (node (ref "EPD_C5") (pin "2") (pinfunction "2_2") (pintype "passive"))
      (node (ref "J1") (pin "15") (pinfunction "15_15") (pintype "bidirectional"))
      (node (ref "J1") (pin "16") (pinfunction "16_16") (pintype "bidirectional"))
      (node (ref "L5") (pin "2") (pinfunction "2_2") (pintype "passive"))
    )
    (net (code "13") (name "EPD_BUSY{slash}1.5D") (class "Default")
      (node (ref "J1") (pin "9") (pinfunction "9_9") (pintype "bidirectional"))
    )
    (net (code "14") (name "EPD_BUSY{slash}2.2D") (class "Default")
      (node (ref "U1") (pin "P$AD12") (pinfunction "P0.17_P$AD12") (pintype "bidirectional"))
    )
    (net (code "15") (name "EPD_CS{slash}1.4C") (class "Default")
      (node (ref "J1") (pin "12") (pinfunction "12_12") (pintype "bidirectional"))
    )
    (net (code "16") (name "EPD_CS{slash}2.2D") (class "Default")
      (node (ref "U1") (pin "P$K2") (pinfunction "P0.05/AIN3_P$K2") (pintype "bidirectional"))
    )
    (net (code "17") (name "EPD_DC{slash}1.5D") (class "Default")
      (node (ref "J1") (pin "11") (pinfunction "11_11") (pintype "bidirectional"))
    )
    (net (code "18") (name "EPD_DC{slash}2.2D") (class "Default")
      (node (ref "U1") (pin "P$AD10") (pinfunction "P0.15_P$AD10") (pintype "bidirectional"))
    )
    (net (code "19") (name "EPD_RST{slash}1.5D") (class "Default")
      (node (ref "J1") (pin "10") (pinfunction "10_10") (pintype "bidirectional"))
    )
    (net (code "20") (name "EPD_RST{slash}2.2D") (class "Default")
      (node (ref "U1") (pin "P$AC11") (pinfunction "P0.16_P$AC11") (pintype "bidirectional"))
    )
    (net (code "21") (name "GDR") (class "Default")
      (node (ref "J1") (pin "2") (pinfunction "2_2") (pintype "bidirectional"))
      (node (ref "Q3") (pin "1") (pinfunction "G_1") (pintype "bidirectional"))
      (node (ref "R2_EP_DR") (pin "2") (pinfunction "2_2") (pintype "bidirectional"))
    )
    (net (code "22") (name "GND") (class "Default")
      (node (ref "C1") (pin "2") (pinfunction "2_2") (pintype "passive"))
      (node (ref "C1-EP-DR") (pin "2") (pinfunction "2_2") (pintype "passive"))
      (node (ref "C10") (pin "2") (pinfunction "2_2") (pintype "passive"))
      (node (ref "C11") (pin "2") (pinfunction "2_2") (pintype "passive"))
      (node (ref "C12") (pin "2") (pinfunction "2_2") (pintype "passive"))
      (node (ref "C13") (pin "2") (pinfunction "2_2") (pintype "passive"))
      (node (ref "C14") (pin "2") (pinfunction "2_2") (pintype "passive"))
      (node (ref "C15") (pin "2") (pinfunction "2_2") (pintype "passive"))
      (node (ref "C16") (pin "2") (pinfunction "2_2") (pintype "passive"))
      (node (ref "C17") (pin "1") (pinfunction "1_1") (pintype "passive"))
      (node (ref "C18") (pin "1") (pinfunction "1_1") (pintype "passive"))
      (node (ref "C19") (pin "2") (pinfunction "2_2") (pintype "passive"))
      (node (ref "C2") (pin "2") (pinfunction "2_2") (pintype "passive"))
      (node (ref "C20") (pin "2") (pinfunction "2_2") (pintype "passive"))
      (node (ref "C21") (pin "2") (pinfunction "2_2") (pintype "passive"))
      (node (ref "C22") (pin "2") (pinfunction "2_2") (pintype "passive"))
      (node (ref "C23") (pin "1") (pinfunction "1_1") (pintype "passive"))
      (node (ref "C24") (pin "1") (pinfunction "1_1") (pintype "passive"))
      (node (ref "C25") (pin "2") (pinfunction "2_2") (pintype "passive"))
      (node (ref "C27") (pin "1") (pinfunction "1_1") (pintype "passive"))
      (node (ref "C29") (pin "1") (pinfunction "1_1") (pintype "passive"))
      (node (ref "C3") (pin "2") (pinfunction "2_2") (pintype "passive"))
      (node (ref "C30") (pin "1") (pinfunction "1_1") (pintype "passive"))
      (node (ref "C31") (pin "1") (pinfunction "1_1") (pintype "passive"))
      (node (ref "C32") (pin "1") (pinfunction "1_1") (pintype "passive"))
      (node (ref "C33") (pin "2") (pinfunction "2_2") (pintype "passive"))
      (node (ref "C34") (pin "1") (pinfunction "1_1") (pintype "passive"))
      (node (ref "C37") (pin "1") (pinfunction "1_1") (pintype "passive"))
      (node (ref "C38") (pin "1") (pinfunction "1_1") (pintype "passive"))
      (node (ref "C39") (pin "2") (pinfunction "2_2") (pintype "passive"))
      (node (ref "C4") (pin "2") (pinfunction "2_2") (pintype "passive"))
      (node (ref "C42") (pin "2") (pinfunction "2_2") (pintype "passive"))
      (node (ref "C43") (pin "2") (pinfunction "2_2") (pintype "passive"))
      (node (ref "C5") (pin "2") (pinfunction "2_2") (pintype "passive"))
      (node (ref "C6") (pin "2") (pinfunction "2_2") (pintype "passive"))
      (node (ref "C7") (pin "2") (pinfunction "2_2") (pintype "passive"))
      (node (ref "C8") (pin "2") (pinfunction "2_2") (pintype "passive"))
      (node (ref "C9") (pin "2") (pinfunction "2_2") (pintype "passive"))
      (node (ref "D3") (pin "2") (pinfunction "GND_2") (pintype "bidirectional"))
      (node (ref "D4") (pin "1") (pinfunction "K_1") (pintype "bidirectional"))
      (node (ref "EPD_C1") (pin "1") (pinfunction "1_1") (pintype "passive"))
      (node (ref "EPD_C10") (pin "1") (pinfunction "1_1") (pintype "passive"))
      (node (ref "EPD_C11") (pin "1") (pinfunction "1_1") (pintype "passive"))
      (node (ref "EPD_C12") (pin "1") (pinfunction "1_1") (pintype "passive"))
      (node (ref "EPD_C2") (pin "1") (pinfunction "1_1") (pintype "passive"))
      (node (ref "EPD_C5") (pin "1") (pinfunction "1_1") (pintype "passive"))
      (node (ref "EPD_C6") (pin "1") (pinfunction "1_1") (pintype "passive"))
      (node (ref "EPD_C7") (pin "1") (pinfunction "1_1") (pintype "passive"))
      (node (ref "EPD_C8") (pin "1") (pinfunction "1_1") (pintype "passive"))
      (node (ref "EPD_C9") (pin "1") (pinfunction "1_1") (pintype "passive"))
      (node (ref "IC1") (pin "D2") (pinfunction "GND_D2") (pintype "bidirectional"))
      (node (ref "IC2") (pin "B1") (pinfunction "IN/TRIG_B1") (pintype "bidirectional"))
      (node (ref "IC2") (pin "B3") (pinfunction "GND_B3") (pintype "bidirectional"))
      (node (ref "IC3") (pin "8") (pinfunction "GNDIO_8") (pintype "bidirectional"))
      (node (ref "IC3") (pin "9") (pinfunction "GND_9") (pintype "bidirectional"))
      (node (ref "IC9") (pin "B1") (pinfunction "VSEL_B1") (pintype "bidirectional"))
      (node (ref "IC9") (pin "C1") (pinfunction "AGND_C1") (pintype "bidirectional"))
      (node (ref "IC9") (pin "C2") (pinfunction "PGND_1_C2") (pintype "bidirectional"))
      (node (ref "IC9") (pin "C3") (pinfunction "PGND_2_C3") (pintype "bidirectional"))
      (node (ref "J1") (pin "17") (pinfunction "17_17") (pintype "bidirectional"))
      (node (ref "J1") (pin "8") (pinfunction "8_8") (pintype "bidirectional"))
      (node (ref "J1") (pin "MP1") (pinfunction "MP1_MP1") (pintype "bidirectional"))
      (node (ref "J1") (pin "MP2") (pinfunction "MP2_MP2") (pintype "bidirectional"))
      (node (ref "J2") (pin "3") (pinfunction "3_3") (pintype "bidirectional"))
      (node (ref "J2") (pin "5") (pinfunction "5_5") (pintype "bidirectional"))
      (node (ref "J4") (pin "A12_B1") (pinfunction "GND_A12_B1") (pintype "power_in"))
      (node (ref "J4") (pin "A1_B12") (pinfunction "GND_A1_B12") (pintype "power_in"))
      (node (ref "J4") (pin "SH1") (pinfunction "SHIELD_SH1") (pintype "passive"))
      (node (ref "J4") (pin "SH2") (pinfunction "SHIELD_SH2") (pintype "passive"))
      (node (ref "J4") (pin "SH3") (pinfunction "SHIELD_SH3") (pintype "passive"))
      (node (ref "J4") (pin "SH4") (pinfunction "SHIELD_SH4") (pintype "passive"))
      (node (ref "R1_USB") (pin "1") (pinfunction "1_1") (pintype "bidirectional"))
      (node (ref "R2_EP_DR") (pin "1") (pinfunction "1_1") (pintype "bidirectional"))
      (node (ref "R2_USB") (pin "2") (pinfunction "2_2") (pintype "bidirectional"))
      (node (ref "R3") (pin "1") (pinfunction "1_1") (pintype "bidirectional"))
      (node (ref "R9") (pin "1") (pinfunction "1_1") (pintype "bidirectional"))
      (node (ref "R_TYPE_SEL") (pin "1") (pinfunction "1_1") (pintype "bidirectional"))
      (node (ref "SJ1") (pin "1") (pinfunction "1_1") (pintype "passive"))
      (node (ref "SW_DN") (pin "1") (pinfunction "1_1") (pintype "passive"))
      (node (ref "SW_ENT") (pin "1") (pinfunction "1_1") (pintype "passive"))
      (node (ref "SW_UP") (pin "1") (pinfunction "1_1") (pintype "passive"))
      (node (ref "TP_BAT_GND") (pin "TP") (pinfunction "TP_TP") (pintype "input"))
      (node (ref "TP_GND") (pin "TP") (pinfunction "TP_TP") (pintype "input"))
      (node (ref "U1") (pin "P$74") (pinfunction "VSS_PAD_P$74") (pintype "bidirectional"))
      (node (ref "U1") (pin "P$75") (pinfunction "VSS_PAD_P$75") (pintype "bidirectional"))
      (node (ref "U1") (pin "P$76") (pinfunction "VSS_PAD_P$76") (pintype "bidirectional"))
      (node (ref "U1") (pin "P$77") (pinfunction "VSS_PAD_P$77") (pintype "bidirectional"))
      (node (ref "U1") (pin "P$78") (pinfunction "VSS_PAD_P$78") (pintype "bidirectional"))
      (node (ref "U1") (pin "P$79") (pinfunction "VSS_PAD_P$79") (pintype "bidirectional"))
      (node (ref "U1") (pin "P$80") (pinfunction "VSS_PAD_P$80") (pintype "bidirectional"))
      (node (ref "U1") (pin "P$81") (pinfunction "VSS_PAD_P$81") (pintype "bidirectional"))
      (node (ref "U1") (pin "P$82") (pinfunction "VSS_PAD_P$82") (pintype "bidirectional"))
      (node (ref "U1") (pin "P$83") (pinfunction "VSS_PAD_P$83") (pintype "bidirectional"))
      (node (ref "U1") (pin "P$84") (pinfunction "VSS_PAD_P$84") (pintype "bidirectional"))
      (node (ref "U1") (pin "P$85") (pinfunction "VSS_PAD_P$85") (pintype "bidirectional"))
      (node (ref "U1") (pin "P$86") (pinfunction "VSS_PAD_P$86") (pintype "bidirectional"))
      (node (ref "U1") (pin "P$87") (pinfunction "VSS_PAD_P$87") (pintype "bidirectional"))
      (node (ref "U1") (pin "P$88") (pinfunction "VSS_PAD_P$88") (pintype "bidirectional"))
      (node (ref "U1") (pin "P$89") (pinfunction "VSS_PAD_P$89") (pintype "bidirectional"))
      (node (ref "U1") (pin "P$90") (pinfunction "VSS_PAD_P$90") (pintype "bidirectional"))
      (node (ref "U1") (pin "P$B7") (pinfunction "VSS_P$B7") (pintype "power_in"))
      (node (ref "U1") (pin "P$F23") (pinfunction "VSS_PA_P$F23") (pintype "bidirectional"))
      (node (ref "U3") (pin "1") (pinfunction "CTG_1") (pintype "power_in"))
      (node (ref "U3") (pin "4") (pinfunction "GND_4") (pintype "power_in"))
      (node (ref "U3") (pin "6") (pinfunction "QSTRT_6") (pintype "input"))
      (node (ref "U3") (pin "9") (pinfunction "EP_9") (pintype "power_in"))
      (node (ref "X1") (pin "2") (pinfunction "2_2") (pintype "passive"))
      (node (ref "X1") (pin "4") (pinfunction "4_4") (pintype "passive"))
    )
    (net (code "23") (name "HAPTIC_EN{slash}1.4C") (class "Default")
      (node (ref "IC2") (pin "A1") (pinfunction "EN_A1") (pintype "bidirectional"))
    )
    (net (code "24") (name "HAPTIC_EN{slash}2.6A") (class "Default")
      (node (ref "U1") (pin "P$U1") (pinfunction "P0.12_P$U1") (pintype "bidirectional"))
    )
    (net (code "25") (name "IMU_INT1") (class "Default")
      (node (ref "IC3") (pin "5") (pinfunction "INT1_5") (pintype "bidirectional"))
      (node (ref "U1") (pin "P$N1") (pinfunction "P0.08_P$N1") (pintype "bidirectional"))
    )
    (net (code "26") (name "IMU_INT2") (class "Default")
      (node (ref "IC3") (pin "6") (pinfunction "INT2_6") (pintype "bidirectional"))
      (node (ref "U1") (pin "P$P2") (pinfunction "P1.08_P$P2") (pintype "bidirectional"))
    )
    (net (code "27") (name "LX1") (class "Default")
      (node (ref "IC9") (pin "B2") (pinfunction "SW1_1_B2") (pintype "bidirectional"))
      (node (ref "IC9") (pin "B3") (pinfunction "SW1_2_B3") (pintype "bidirectional"))
      (node (ref "L7") (pin "1") (pinfunction "1_1") (pintype "bidirectional"))
    )
    (net (code "28") (name "LX2") (class "Default")
      (node (ref "IC9") (pin "D2") (pinfunction "SW2_1_D2") (pintype "bidirectional"))
      (node (ref "IC9") (pin "D3") (pinfunction "SW2_2_D3") (pintype "bidirectional"))
      (node (ref "L7") (pin "2") (pinfunction "2_2") (pintype "bidirectional"))
    )
    (net (code "29") (name "MOSI{slash}1.5B") (class "Default")
      (node (ref "J1") (pin "14") (pinfunction "14_14") (pintype "bidirectional"))
    )
    (net (code "30") (name "MOSI{slash}2.2D") (class "Default")
      (node (ref "U1") (pin "P$B13") (pinfunction "P0.03/AIN1_P$B13") (pintype "bidirectional"))
    )
    (net (code "31") (name "Net-(ANT1-FEED)") (class "Default")
      (node (ref "ANT1") (pin "1") (pinfunction "FEED_1") (pintype "input"))
      (node (ref "C22") (pin "1") (pinfunction "1_1") (pintype "passive"))
      (node (ref "C4") (pin "1") (pinfunction "1_1") (pintype "passive"))
      (node (ref "L1") (pin "2") (pinfunction "2_2") (pintype "passive"))
    )
    (net (code "32") (name "Net-(D2-K)") (class "Default")
      (node (ref "C2-EP-DR") (pin "1") (pinfunction "1_1") (pintype "passive"))
      (node (ref "D2") (pin "1") (pinfunction "K_1") (pintype "bidirectional"))
      (node (ref "D4") (pin "2") (pinfunction "A_2") (pintype "bidirectional"))
    )
    (net (code "33") (name "Net-(D5-A)") (class "Default")
      (node (ref "C2-EP-DR") (pin "2") (pinfunction "2_2") (pintype "passive"))
      (node (ref "D5") (pin "2") (pinfunction "A_2") (pintype "bidirectional"))
      (node (ref "L5") (pin "1") (pinfunction "1_1") (pintype "passive"))
      (node (ref "Q3") (pin "3") (pinfunction "D_3") (pintype "bidirectional"))
    )
    (net (code "34") (name "Net-(EPD_C1-Pad2)") (class "Default")
      (node (ref "EPD_C1") (pin "2") (pinfunction "2_2") (pintype "passive"))
      (node (ref "J1") (pin "5") (pinfunction "5_5") (pintype "bidirectional"))
    )
    (net (code "35") (name "Net-(EPD_C2-Pad2)") (class "Default")
      (node (ref "EPD_C2") (pin "2") (pinfunction "2_2") (pintype "passive"))
      (node (ref "J1") (pin "4") (pinfunction "4_4") (pintype "bidirectional"))
    )
    (net (code "36") (name "Net-(EPD_C6-Pad2)") (class "Default")
      (node (ref "EPD_C6") (pin "2") (pinfunction "2_2") (pintype "passive"))
      (node (ref "J1") (pin "18") (pinfunction "18_18") (pintype "bidirectional"))
    )
    (net (code "37") (name "Net-(EPD_C7-Pad2)") (class "Default")
      (node (ref "EPD_C7") (pin "2") (pinfunction "2_2") (pintype "passive"))
      (node (ref "J1") (pin "19") (pinfunction "19_19") (pintype "bidirectional"))
    )
    (net (code "38") (name "Net-(EPD_C8-Pad2)") (class "Default")
      (node (ref "EPD_C8") (pin "2") (pinfunction "2_2") (pintype "passive"))
      (node (ref "J1") (pin "20") (pinfunction "20_20") (pintype "bidirectional"))
    )
    (net (code "39") (name "Net-(EPD_C10-Pad2)") (class "Default")
      (node (ref "EPD_C10") (pin "2") (pinfunction "2_2") (pintype "passive"))
      (node (ref "J1") (pin "22") (pinfunction "22_22") (pintype "bidirectional"))
    )
    (net (code "40") (name "Net-(EPD_C12-Pad2)") (class "Default")
      (node (ref "EPD_C12") (pin "2") (pinfunction "2_2") (pintype "passive"))
      (node (ref "J1") (pin "24") (pinfunction "24_24") (pintype "bidirectional"))
    )
    (net (code "41") (name "Net-(IC1-TS{slash}MR)") (class "Default")
      (node (ref "IC1") (pin "D1") (pinfunction "TS/MR_D1") (pintype "bidirectional"))
      (node (ref "R9") (pin "2") (pinfunction "2_2") (pintype "bidirectional"))
    )
    (net (code "42") (name "Net-(IC2-REG)") (class "Default")
      (node (ref "C32") (pin "2") (pinfunction "2_2") (pintype "passive"))
      (node (ref "IC2") (pin "A2") (pinfunction "REG_A2") (pintype "bidirectional"))
    )
    (net (code "43") (name "Net-(IC3-SDO)") (class "Default")
      (node (ref "IC3") (pin "1") (pinfunction "SDO_1") (pintype "bidirectional"))
      (node (ref "R3") (pin "2") (pinfunction "2_2") (pintype "bidirectional"))
    )
    (net (code "44") (name "Net-(IC9-SCL)") (class "Default")
      (node (ref "IC9") (pin "D1") (pinfunction "SCL_D1") (pintype "bidirectional"))
      (node (ref "R4") (pin "2") (pinfunction "2_2") (pintype "bidirectional"))
    )
    (net (code "45") (name "Net-(IC9-SDA)") (class "Default")
      (node (ref "IC9") (pin "E1") (pinfunction "SDA_E1") (pintype "bidirectional"))
      (node (ref "R2") (pin "2") (pinfunction "2_2") (pintype "bidirectional"))
    )
    (net (code "46") (name "Net-(J4-CC1)") (class "Default")
      (node (ref "J4") (pin "A5") (pinfunction "CC1_A5") (pintype "bidirectional"))
      (node (ref "R1_USB") (pin "2") (pinfunction "2_2") (pintype "bidirectional"))
    )
    (net (code "47") (name "Net-(J4-CC2)") (class "Default")
      (node (ref "J4") (pin "B5") (pinfunction "CC2_B5") (pintype "bidirectional"))
      (node (ref "R2_USB") (pin "1") (pinfunction "1_1") (pintype "bidirectional"))
    )
    (net (code "48") (name "Net-(L2-Pad2)") (class "Default")
      (node (ref "L2") (pin "2") (pinfunction "2_2") (pintype "passive"))
      (node (ref "L3") (pin "1") (pinfunction "1_1") (pintype "passive"))
    )
    (net (code "49") (name "Net-(R1_EP_DR-Pad1)") (class "Default")
      (node (ref "R1_EP_DR") (pin "1") (pinfunction "1_1") (pintype "bidirectional"))
      (node (ref "R_TYPE_SEL") (pin "2") (pinfunction "2_2") (pintype "bidirectional"))
      (node (ref "SJ1") (pin "2") (pinfunction "2_2") (pintype "passive"))
    )
    (net (code "50") (name "Net-(U1-ANT)") (class "Default")
      (node (ref "C3") (pin "1") (pinfunction "1_1") (pintype "passive"))
      (node (ref "L1") (pin "1") (pinfunction "1_1") (pintype "passive"))
      (node (ref "U1") (pin "P$H23") (pinfunction "ANT_P$H23") (pintype "bidirectional"))
    )
    (net (code "51") (name "Net-(U1-DCC)") (class "Default")
      (node (ref "L2") (pin "1") (pinfunction "1_1") (pintype "passive"))
      (node (ref "U1") (pin "P$B3") (pinfunction "DCC_P$B3") (pintype "output"))
    )
    (net (code "52") (name "Net-(U1-DEC1)") (class "Default")
      (node (ref "C5") (pin "1") (pinfunction "1_1") (pintype "passive"))
      (node (ref "U1") (pin "P$C1") (pinfunction "DEC1_P$C1") (pintype "power_in"))
    )
    (net (code "53") (name "Net-(U1-DEC2)") (class "Default")
      (node (ref "C13") (pin "1") (pinfunction "1_1") (pintype "passive"))
      (node (ref "U1") (pin "P$A18") (pinfunction "DEC2_P$A18") (pintype "bidirectional"))
    )
    (net (code "54") (name "Net-(U1-DEC3)") (class "Default")
      (node (ref "C11") (pin "1") (pinfunction "1_1") (pintype "passive"))
      (node (ref "U1") (pin "P$D23") (pinfunction "DEC3_P$D23") (pintype "bidirectional"))
    )
    (net (code "55") (name "Net-(U1-DEC3V3)") (class "Default")
      (node (ref "C20") (pin "1") (pinfunction "1_1") (pintype "passive"))
      (node (ref "U1") (pin "P$AC5") (pinfunction "DEC3V3_P$AC5") (pintype "bidirectional"))
    )
    (net (code "56") (name "Net-(U1-DEC5)") (class "Default")
      (node (ref "C9") (pin "1") (pinfunction "1_1") (pintype "passive"))
      (node (ref "U1") (pin "P$N24") (pinfunction "DEC5_P$N24") (pintype "bidirectional"))
    )
    (net (code "57") (name "Net-(U1-XC1)") (class "Default")
      (node (ref "C1") (pin "1") (pinfunction "1_1") (pintype "passive"))
      (node (ref "U1") (pin "P$B24") (pinfunction "XC1_P$B24") (pintype "input"))
      (node (ref "X1") (pin "1") (pinfunction "1_1") (pintype "passive"))
    )
    (net (code "58") (name "Net-(U1-XC2)") (class "Default")
      (node (ref "C2") (pin "1") (pinfunction "1_1") (pintype "passive"))
      (node (ref "U1") (pin "P$A23") (pinfunction "XC2_P$A23") (pintype "output"))
      (node (ref "X1") (pin "3") (pinfunction "3_3") (pintype "passive"))
    )
    (net (code "59") (name "OUT+") (class "Default")
      (node (ref "IC2") (pin "A3") (pinfunction "OUT+_A3") (pintype "bidirectional"))
      (node (ref "TP_OP") (pin "TP") (pinfunction "TP_TP") (pintype "input"))
    )
    (net (code "60") (name "OUT-") (class "Default")
      (node (ref "IC2") (pin "C3") (pinfunction "OUT-_C3") (pintype "bidirectional"))
      (node (ref "TP_ON") (pin "TP") (pinfunction "TP_TP") (pintype "input"))
    )
    (net (code "61") (name "P0.00{slash}XL1") (class "Default")
      (node (ref "C17") (pin "2") (pinfunction "2_2") (pintype "passive"))
      (node (ref "U1") (pin "P$D2") (pinfunction "P0.00/XL1_P$D2") (pintype "bidirectional"))
      (node (ref "X2") (pin "1") (pinfunction "1_1") (pintype "passive"))
    )
    (net (code "62") (name "P0.01{slash}XL2") (class "Default")
      (node (ref "C18") (pin "2") (pinfunction "2_2") (pintype "passive"))
      (node (ref "U1") (pin "P$F2") (pinfunction "P0.01/XL2_P$F2") (pintype "bidirectional"))
      (node (ref "X2") (pin "2") (pinfunction "2_2") (pintype "passive"))
    )
    (net (code "63") (name "P0.04") (class "Default")
      (node (ref "U1") (pin "P$J1") (pinfunction "P0.04/AIN2_P$J1") (pintype "bidirectional"))
    )
    (net (code "64") (name "P0.09") (class "Default")
      (node (ref "U1") (pin "P$L24") (pinfunction "P0.09/NFC1_P$L24") (pintype "bidirectional"))
    )
    (net (code "65") (name "P0.13{slash}1.5D") (class "Default")
      (node (ref "C30") (pin "2") (pinfunction "2_2") (pintype "passive"))
      (node (ref "R5") (pin "1") (pinfunction "1_1") (pintype "bidirectional"))
      (node (ref "SW_UP") (pin "2") (pinfunction "2_2") (pintype "passive"))
    )
    (net (code "66") (name "P0.13{slash}2.6C") (class "Default")
      (node (ref "U1") (pin "P$AD8") (pinfunction "P0.13_P$AD8") (pintype "bidirectional"))
    )
    (net (code "67") (name "P0.14{slash}1.5D") (class "Default")
      (node (ref "C31") (pin "2") (pinfunction "2_2") (pintype "passive"))
      (node (ref "R8") (pin "1") (pinfunction "1_1") (pintype "bidirectional"))
      (node (ref "SW_ENT") (pin "2") (pinfunction "2_2") (pintype "passive"))
    )
    (net (code "68") (name "P0.14{slash}2.7C") (class "Default")
      (node (ref "U1") (pin "P$AC9") (pinfunction "P0.14_P$AC9") (pintype "bidirectional"))
    )
    (net (code "69") (name "P0.19") (class "Default")
      (node (ref "U1") (pin "P$AC15") (pinfunction "P0.19_P$AC15") (pintype "bidirectional"))
    )
    (net (code "70") (name "P0.20") (class "Default")
      (node (ref "U1") (pin "P$AD16") (pinfunction "P0.20_P$AD16") (pintype "bidirectional"))
    )
    (net (code "71") (name "P0.21") (class "Default")
      (node (ref "U1") (pin "P$AC17") (pinfunction "P0.21_P$AC17") (pintype "bidirectional"))
    )
    (net (code "72") (name "P0.22") (class "Default")
      (node (ref "U1") (pin "P$AD18") (pinfunction "P0.22_P$AD18") (pintype "bidirectional"))
    )
    (net (code "73") (name "P0.23") (class "Default")
      (node (ref "U1") (pin "P$AC19") (pinfunction "P0.23_P$AC19") (pintype "bidirectional"))
    )
    (net (code "74") (name "P0.24") (class "Default")
      (node (ref "U1") (pin "P$AD20") (pinfunction "P0.24_P$AD20") (pintype "bidirectional"))
    )
    (net (code "75") (name "P0.25") (class "Default")
      (node (ref "U1") (pin "P$AC21") (pinfunction "P0.25_P$AC21") (pintype "bidirectional"))
    )
    (net (code "76") (name "P0.26") (class "Default")
      (node (ref "U1") (pin "P$G1") (pinfunction "P0.26_P$G1") (pintype "bidirectional"))
    )
    (net (code "77") (name "P0.27") (class "Default")
      (node (ref "U1") (pin "P$H2") (pinfunction "P0.27_P$H2") (pintype "bidirectional"))
    )
    (net (code "78") (name "P0.28") (class "Default")
      (node (ref "U1") (pin "P$B11") (pinfunction "P0.28/AIN4_P$B11") (pintype "bidirectional"))
    )
    (net (code "79") (name "P0.29") (class "Default")
      (node (ref "U1") (pin "P$A10") (pinfunction "P0.29/AIN5_P$A10") (pintype "bidirectional"))
    )
    (net (code "80") (name "P0.30") (class "Default")
      (node (ref "U1") (pin "P$B9") (pinfunction "P0.30/AIN6_P$B9") (pintype "bidirectional"))
    )
    (net (code "81") (name "P0.31") (class "Default")
      (node (ref "U1") (pin "P$A8") (pinfunction "P0.31/AIN7_P$A8") (pintype "bidirectional"))
    )
    (net (code "82") (name "P1.01{slash}1.6C") (class "Default")
      (node (ref "DMG2305UX-7") (pin "1") (pinfunction "G_1") (pintype "bidirectional"))
      (node (ref "R_PWR_EPD") (pin "1") (pinfunction "1_1") (pintype "bidirectional"))
    )
    (net (code "83") (name "P1.01{slash}2.4B") (class "Default")
      (node (ref "U1") (pin "P$Y23") (pinfunction "P1.01_P$Y23") (pintype "bidirectional"))
    )
    (net (code "84") (name "P1.02{slash}1.6C") (class "Default")
      (node (ref "C29") (pin "2") (pinfunction "2_2") (pintype "passive"))
      (node (ref "R7") (pin "1") (pinfunction "1_1") (pintype "bidirectional"))
      (node (ref "SW_DN") (pin "2") (pinfunction "2_2") (pintype "passive"))
    )
    (net (code "85") (name "P1.02{slash}2.8C") (class "Default")
      (node (ref "U1") (pin "P$W24") (pinfunction "P1.02_P$W24") (pintype "bidirectional"))
    )
    (net (code "86") (name "P1.03") (class "Default")
      (node (ref "U1") (pin "P$V23") (pinfunction "P1.03_P$V23") (pintype "bidirectional"))
    )
    (net (code "87") (name "P1.04") (class "Default")
      (node (ref "U1") (pin "P$U24") (pinfunction "P1.04_P$U24") (pintype "bidirectional"))
    )
    (net (code "88") (name "P1.05") (class "Default")
      (node (ref "U1") (pin "P$T23") (pinfunction "P1.05_P$T23") (pintype "bidirectional"))
    )
    (net (code "89") (name "P1.06") (class "Default")
      (node (ref "U1") (pin "P$R24") (pinfunction "P1.06_P$R24") (pintype "bidirectional"))
    )
    (net (code "90") (name "P1.07") (class "Default")
      (node (ref "U1") (pin "P$P23") (pinfunction "P1.07_P$P23") (pintype "bidirectional"))
    )
    (net (code "91") (name "P1.09") (class "Default")
      (node (ref "U1") (pin "P$R1") (pinfunction "P1.09_P$R1") (pintype "bidirectional"))
    )
    (net (code "92") (name "P1.10") (class "Default")
      (node (ref "U1") (pin "P$A20") (pinfunction "P1.10_P$A20") (pintype "bidirectional"))
    )
    (net (code "93") (name "P1.11") (class "Default")
      (node (ref "U1") (pin "P$B19") (pinfunction "P1.11_P$B19") (pintype "bidirectional"))
    )
    (net (code "94") (name "P1.12") (class "Default")
      (node (ref "U1") (pin "P$B17") (pinfunction "P1.12_P$B17") (pintype "bidirectional"))
    )
    (net (code "95") (name "P1.13") (class "Default")
      (node (ref "U1") (pin "P$A16") (pinfunction "P1.13_P$A16") (pintype "bidirectional"))
    )
    (net (code "96") (name "P1.14") (class "Default")
      (node (ref "U1") (pin "P$B15") (pinfunction "P1.14_P$B15") (pintype "bidirectional"))
    )
    (net (code "97") (name "P1.15") (class "Default")
      (node (ref "U1") (pin "P$A14") (pinfunction "P1.15_P$A14") (pintype "bidirectional"))
    )
    (net (code "98") (name "PMIC_INT") (class "Default")
      (node (ref "IC1") (pin "A1") (pinfunction "~{INT}_A1") (pintype "bidirectional"))
      (node (ref "U1") (pin "P$T2") (pinfunction "P0.11_P$T2") (pintype "bidirectional"))
    )
    (net (code "99") (name "PREVGH") (class "Default")
      (node (ref "D5") (pin "1") (pinfunction "K_1") (pintype "bidirectional"))
      (node (ref "EPD_C9") (pin "2") (pinfunction "2_2") (pintype "passive"))
      (node (ref "J1") (pin "21") (pinfunction "21_21") (pintype "bidirectional"))
    )
    (net (code "100") (name "PREVGL") (class "Default")
      (node (ref "D2") (pin "2") (pinfunction "A_2") (pintype "bidirectional"))
      (node (ref "EPD_C11") (pin "2") (pinfunction "2_2") (pintype "passive"))
      (node (ref "J1") (pin "23") (pinfunction "23_23") (pintype "bidirectional"))
    )
    (net (code "101") (name "RESE") (class "Default")
      (node (ref "J1") (pin "3") (pinfunction "3_3") (pintype "bidirectional"))
      (node (ref "Q3") (pin "2") (pinfunction "S_2") (pintype "bidirectional"))
      (node (ref "R1_EP_DR") (pin "2") (pinfunction "2_2") (pintype "bidirectional"))
    )
    (net (code "102") (name "RESET") (class "Default")
      (node (ref "J2") (pin "6") (pinfunction "6_6") (pintype "bidirectional"))
      (node (ref "TP_RESET") (pin "TP") (pinfunction "TP_TP") (pintype "input"))
      (node (ref "U1") (pin "P$AC13") (pinfunction "P0.18/RESET_P$AC13") (pintype "bidirectional"))
    )
    (net (code "103") (name "SCK{slash}1.5B") (class "Default")
      (node (ref "J1") (pin "13") (pinfunction "13_13") (pintype "bidirectional"))
    )
    (net (code "104") (name "SCK{slash}2.2D") (class "Default")
      (node (ref "U1") (pin "P$A12") (pinfunction "P0.02/AIN0_P$A12") (pintype "bidirectional"))
    )
    (net (code "105") (name "SCL{slash}1.4C") (class "Default")
      (node (ref "IC2") (pin "C1") (pinfunction "SCL_C1") (pintype "bidirectional"))
      (node (ref "U3") (pin "7") (pinfunction "SCL_7") (pintype "input"))
    )
    (net (code "106") (name "SCL{slash}2.4C") (class "Default")
      (node (ref "IC1") (pin "B1") (pinfunction "SCL_B1") (pintype "bidirectional"))
      (node (ref "IC3") (pin "12") (pinfunction "SCX_12") (pintype "bidirectional"))
      (node (ref "R17") (pin "2") (pinfunction "2_2") (pintype "bidirectional"))
      (node (ref "R4") (pin "1") (pinfunction "1_1") (pintype "bidirectional"))
      (node (ref "TP_SCL") (pin "TP") (pinfunction "TP_TP") (pintype "input"))
      (node (ref "U1") (pin "P$M2") (pinfunction "P0.07_P$M2") (pintype "bidirectional"))
    )
    (net (code "107") (name "SDA{slash}1.4C") (class "Default")
      (node (ref "IC2") (pin "B2") (pinfunction "SDA_B2") (pintype "bidirectional"))
      (node (ref "U3") (pin "8") (pinfunction "SDA_8") (pintype "bidirectional"))
    )
    (net (code "108") (name "SDA{slash}2.4C") (class "Default")
      (node (ref "IC1") (pin "C1") (pinfunction "SDA_C1") (pintype "bidirectional"))
      (node (ref "IC3") (pin "2") (pinfunction "SDX_2") (pintype "bidirectional"))
      (node (ref "R18") (pin "2") (pinfunction "2_2") (pintype "bidirectional"))
      (node (ref "R2") (pin "1") (pinfunction "1_1") (pintype "bidirectional"))
      (node (ref "TP_SDA") (pin "TP") (pinfunction "TP_TP") (pintype "input"))
      (node (ref "U1") (pin "P$L1") (pinfunction "P0.06_P$L1") (pintype "bidirectional"))
    )
    (net (code "109") (name "SWDCLK") (class "Default")
      (node (ref "J2") (pin "4") (pinfunction "4_4") (pintype "bidirectional"))
      (node (ref "TP_SWDCLK") (pin "TP") (pinfunction "TP_TP") (pintype "input"))
      (node (ref "U1") (pin "P$AA24") (pinfunction "SWDCLK_P$AA24") (pintype "input"))
    )
    (net (code "110") (name "SWDIO") (class "Default")
      (node (ref "J2") (pin "2") (pinfunction "2_2") (pintype "bidirectional"))
      (node (ref "TP_SWDIO") (pin "TP") (pinfunction "TP_TP") (pintype "input"))
      (node (ref "U1") (pin "P$AC24") (pinfunction "SWDIO_P$AC24") (pintype "bidirectional"))
    )
    (net (code "111") (name "SWO") (class "Default")
      (node (ref "TP_SWO") (pin "TP") (pinfunction "TP_TP") (pintype "input"))
      (node (ref "U1") (pin "P$AD22") (pinfunction "P1.00_P$AD22") (pintype "bidirectional"))
    )
    (net (code "112") (name "VBAT{slash}1.2A") (class "Default")
      (node (ref "C27") (pin "2") (pinfunction "2_2") (pintype "passive"))
      (node (ref "TP_VBAT") (pin "TP") (pinfunction "TP_TP") (pintype "input"))
      (node (ref "U3") (pin "2") (pinfunction "CELL_2") (pintype "power_in"))
      (node (ref "U3") (pin "3") (pinfunction "VDD_3") (pintype "power_in"))
    )
    (net (code "113") (name "VBAT{slash}2.5C") (class "Default")
      (node (ref "C37") (pin "2") (pinfunction "2_2") (pintype "passive"))
      (node (ref "IC1") (pin "C2") (pinfunction "BAT_C2") (pintype "bidirectional"))
    )
    (net (code "114") (name "VBUS{slash}1.5D") (class "Default")
      (node (ref "C42") (pin "1") (pinfunction "1_1") (pintype "passive"))
      (node (ref "C43") (pin "1") (pinfunction "1_1") (pintype "passive"))
      (node (ref "D3") (pin "5") (pinfunction "VBUS_5") (pintype "bidirectional"))
      (node (ref "J4") (pin "A4_B9") (pinfunction "VBUS_A4_B9") (pintype "power_in"))
      (node (ref "J4") (pin "A9_B4") (pinfunction "VBUS_A9_B4") (pintype "power_in"))
    )
    (net (code "115") (name "VBUS{slash}2.6D") (class "Default")
      (node (ref "C21") (pin "1") (pinfunction "1_1") (pintype "passive"))
      (node (ref "C38") (pin "2") (pinfunction "2_2") (pintype "passive"))
      (node (ref "IC1") (pin "A2") (pinfunction "IN_A2") (pintype "bidirectional"))
      (node (ref "U1") (pin "P$AD2") (pinfunction "VBUS_P$AD2") (pintype "power_in"))
    )
    (net (code "116") (name "VREG") (class "Default")
      (node (ref "C23") (pin "2") (pinfunction "2_2") (pintype "passive"))
      (node (ref "C24") (pin "2") (pinfunction "2_2") (pintype "passive"))
      (node (ref "C39") (pin "1") (pinfunction "1_1") (pintype "passive"))
      (node (ref "IC1") (pin "B2") (pinfunction "SYS_B2") (pintype "bidirectional"))
      (node (ref "IC9") (pin "A1") (pinfunction "EN_A1") (pintype "bidirectional"))
      (node (ref "IC9") (pin "A2") (pinfunction "VIN_1_A2") (pintype "bidirectional"))
      (node (ref "IC9") (pin "A3") (pinfunction "VIN_2_A3") (pintype "bidirectional"))
      (node (ref "TP_VREG") (pin "TP") (pinfunction "TP_TP") (pintype "input"))
    )
    (net (code "117") (name "unconnected-(ANT1-NC-Pad2)") (class "Default")
      (node (ref "ANT1") (pin "2") (pinfunction "NC_2") (pintype "no_connect"))
    )
    (net (code "118") (name "unconnected-(IC3-ASCL-Pad11)") (class "Default")
      (node (ref "IC3") (pin "11") (pinfunction "ASCL_11") (pintype "bidirectional"))
    )
    (net (code "119") (name "unconnected-(IC3-ASDA-Pad4)") (class "Default")
      (node (ref "IC3") (pin "4") (pinfunction "ASDA_4") (pintype "bidirectional"))
    )
    (net (code "120") (name "unconnected-(J1-Pad1)") (class "Default")
      (node (ref "J1") (pin "1") (pinfunction "1_1") (pintype "bidirectional"))
    )
    (net (code "121") (name "unconnected-(J1-Pad6)") (class "Default")
      (node (ref "J1") (pin "6") (pinfunction "6_6") (pintype "bidirectional"))
    )
    (net (code "122") (name "unconnected-(J1-Pad7)") (class "Default")
      (node (ref "J1") (pin "7") (pinfunction "7_7") (pintype "bidirectional"))
    )
    (net (code "123") (name "unconnected-(J4-SBU1-PadA8)") (class "Default")
      (node (ref "J4") (pin "A8") (pinfunction "SBU1_A8") (pintype "bidirectional"))
    )
    (net (code "124") (name "unconnected-(J4-SBU2-PadB8)") (class "Default")
      (node (ref "J4") (pin "B8") (pinfunction "SBU2_B8") (pintype "bidirectional"))
    )
    (net (code "125") (name "unconnected-(U1-DCCH-PadP$AB2)") (class "Default")
      (node (ref "U1") (pin "P$AB2") (pinfunction "DCCH_P$AB2") (pintype "bidirectional"))
    )
  )
)
